# main_v2.net
KiCad netlist of a schematic drawn in EAGLE
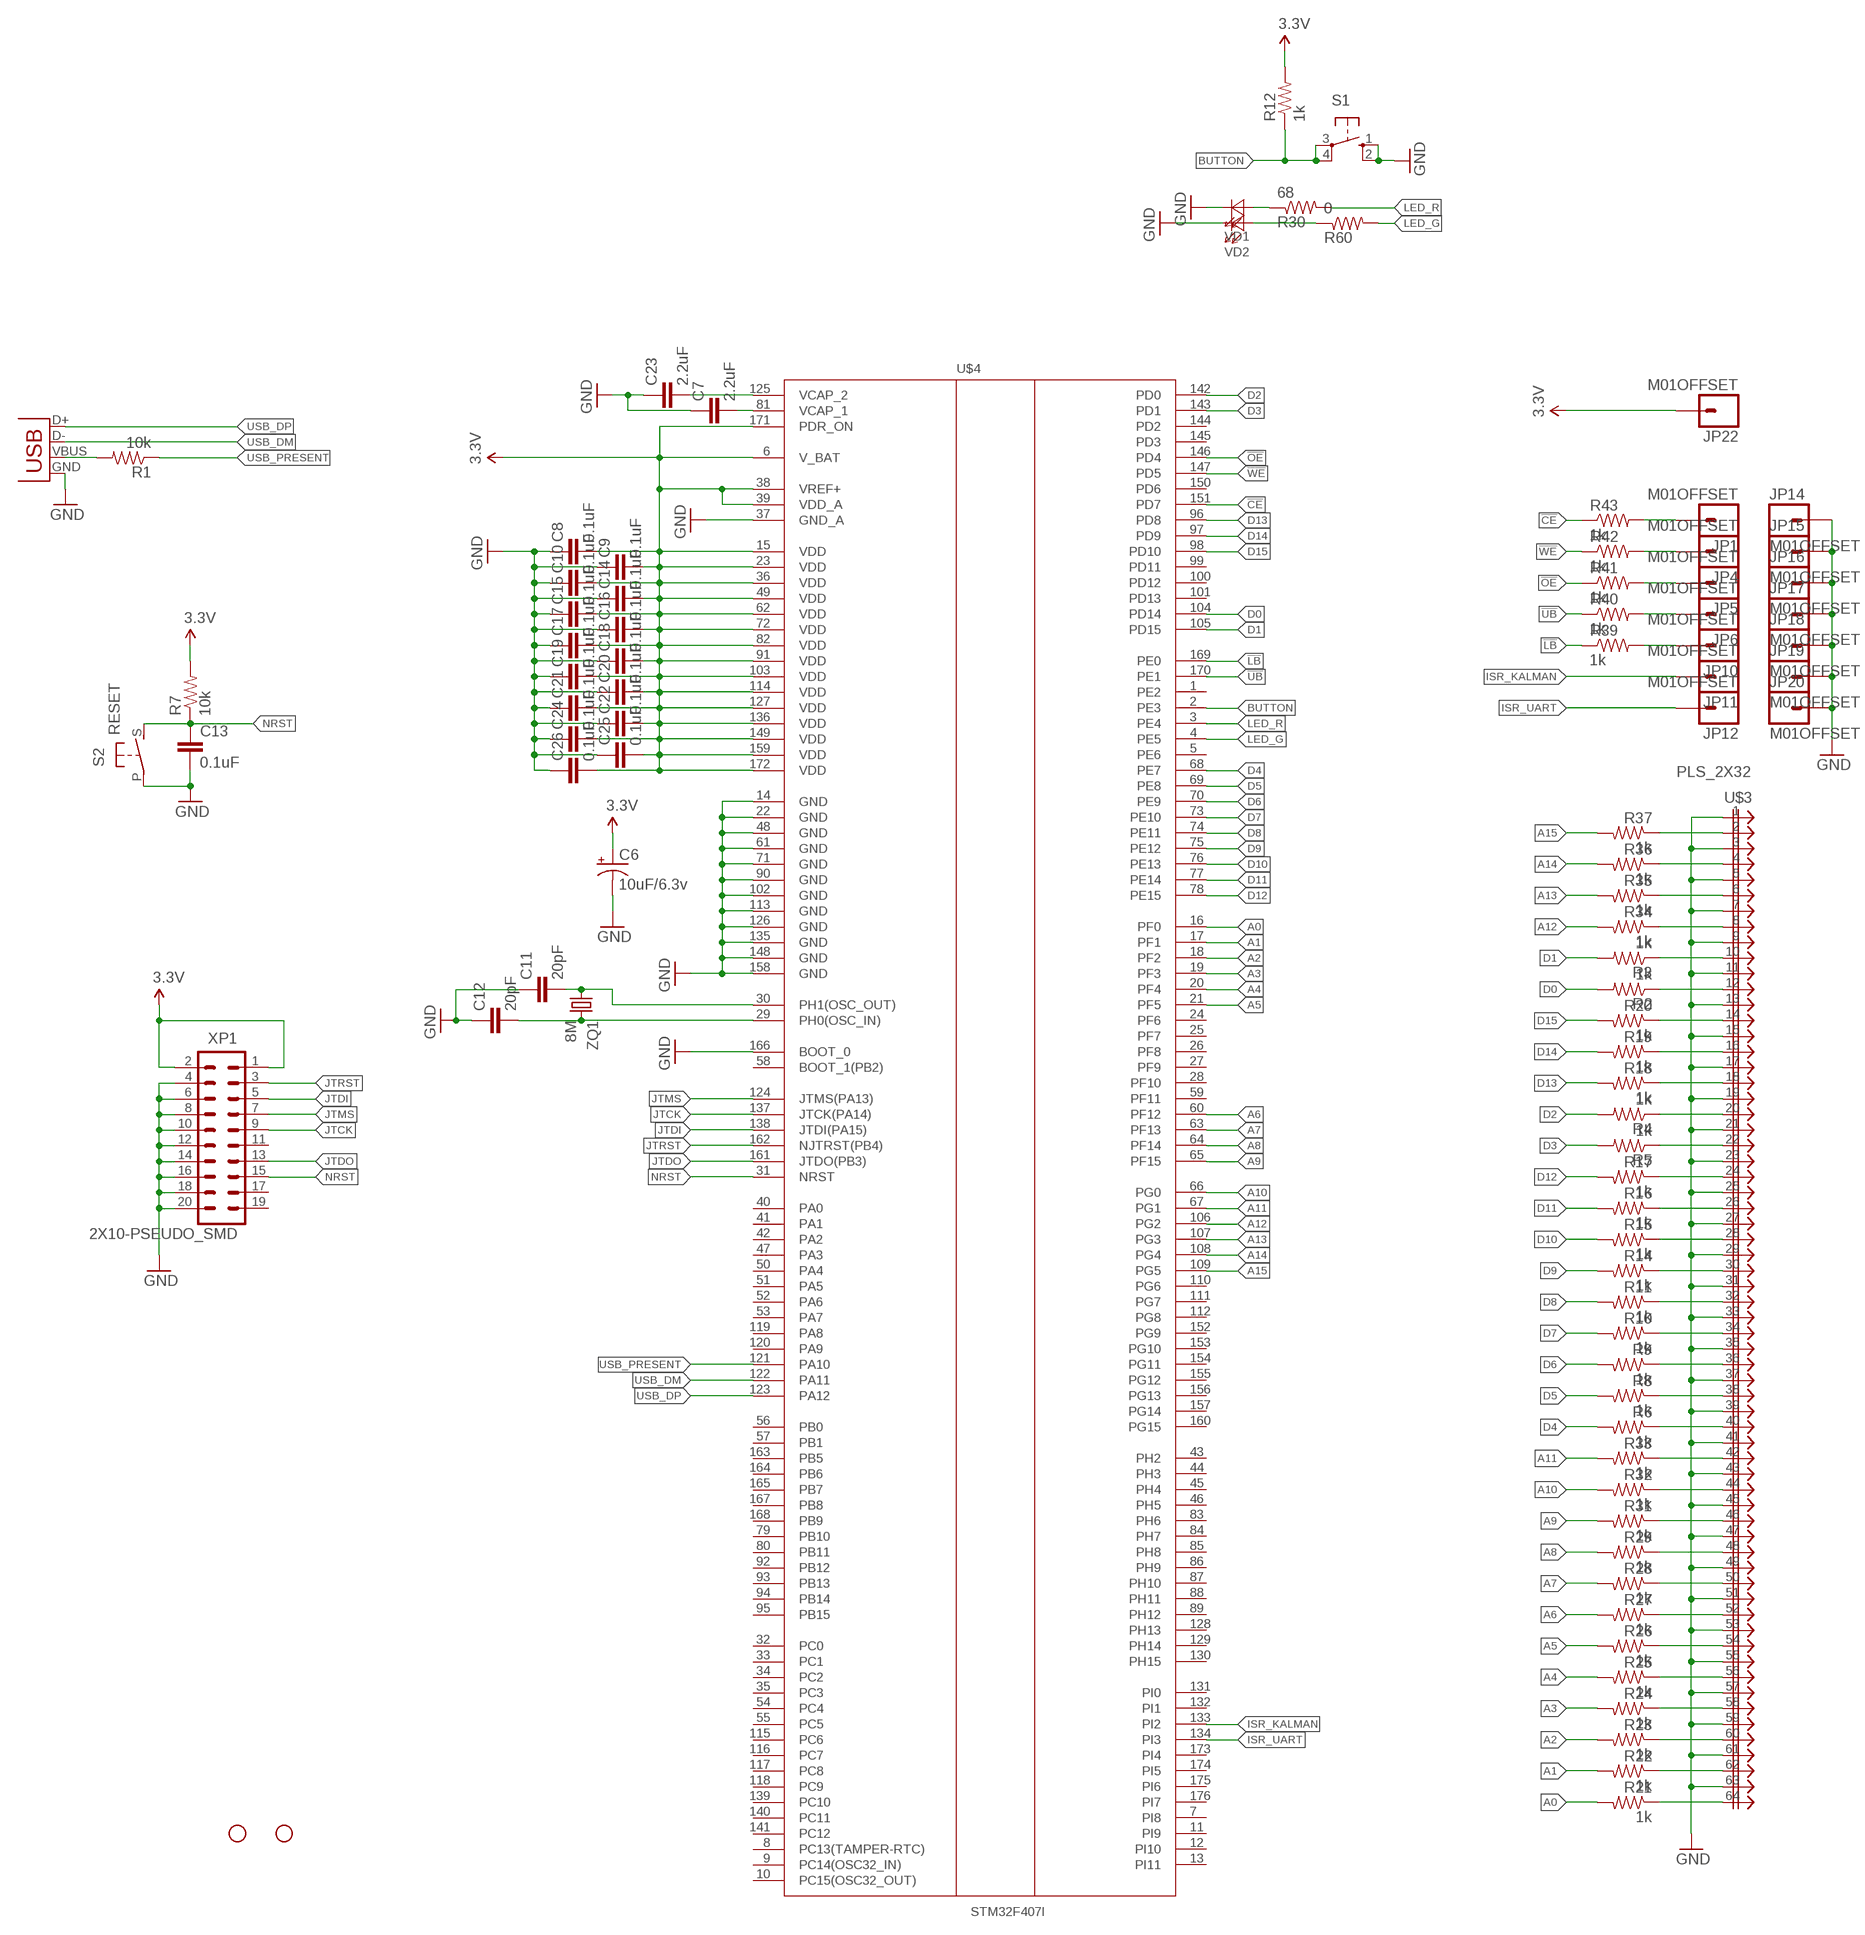
[diagram p0: schematic, sheet 1]

(export (version "E")
  (design (tool "Eeschema 10.0.6"))
  (components
    (comp (ref "C6")
      (value "10uF/6.3v")
      (footprint "eagle-import:EIA3216-KIT")
      (libsource (lib "eagle-import") (part "CAP_POL1206-KIT"))
    )
    (comp (ref "C7")
      (value "2.2uF")
      (footprint "eagle-import:0805")
      (libsource (lib "eagle-import") (part "CAP0805"))
    )
    (comp (ref "C8")
      (value "0.1uF")
      (footprint "eagle-import:0805")
      (libsource (lib "eagle-import") (part "CAP0805"))
    )
    (comp (ref "C9")
      (value "0.1uF")
      (footprint "eagle-import:0805")
      (libsource (lib "eagle-import") (part "CAP0805"))
    )
    (comp (ref "C10")
      (value "0.1uF")
      (footprint "eagle-import:0805")
      (libsource (lib "eagle-import") (part "CAP0805"))
    )
    (comp (ref "C11")
      (value "20pF")
      (footprint "eagle-import:0805")
      (libsource (lib "eagle-import") (part "CAP0805"))
    )
    (comp (ref "C12")
      (value "20pF")
      (footprint "eagle-import:0805")
      (libsource (lib "eagle-import") (part "CAP0805"))
    )
    (comp (ref "C13")
      (value "0.1uF")
      (footprint "eagle-import:0805")
      (libsource (lib "eagle-import") (part "CAP0805"))
    )
    (comp (ref "C14")
      (value "0.1uF")
      (footprint "eagle-import:0805")
      (libsource (lib "eagle-import") (part "CAP0805"))
    )
    (comp (ref "C15")
      (value "0.1uF")
      (footprint "eagle-import:0805")
      (libsource (lib "eagle-import") (part "CAP0805"))
    )
    (comp (ref "C16")
      (value "0.1uF")
      (footprint "eagle-import:0805")
      (libsource (lib "eagle-import") (part "CAP0805"))
    )
    (comp (ref "C17")
      (value "0.1uF")
      (footprint "eagle-import:0805")
      (libsource (lib "eagle-import") (part "CAP0805"))
    )
    (comp (ref "C18")
      (value "0.1uF")
      (footprint "eagle-import:0805")
      (libsource (lib "eagle-import") (part "CAP0805"))
    )
    (comp (ref "C19")
      (value "0.1uF")
      (footprint "eagle-import:0805")
      (libsource (lib "eagle-import") (part "CAP0805"))
    )
    (comp (ref "C20")
      (value "0.1uF")
      (footprint "eagle-import:0805")
      (libsource (lib "eagle-import") (part "CAP0805"))
    )
    (comp (ref "C21")
      (value "0.1uF")
      (footprint "eagle-import:0805")
      (libsource (lib "eagle-import") (part "CAP0805"))
    )
    (comp (ref "C22")
      (value "0.1uF")
      (footprint "eagle-import:0805")
      (libsource (lib "eagle-import") (part "CAP0805"))
    )
    (comp (ref "C23")
      (value "2.2uF")
      (footprint "eagle-import:0805")
      (libsource (lib "eagle-import") (part "CAP0805"))
    )
    (comp (ref "C24")
      (value "0.1uF")
      (footprint "eagle-import:0805")
      (libsource (lib "eagle-import") (part "CAP0805"))
    )
    (comp (ref "C25")
      (value "0.1uF")
      (footprint "eagle-import:0805")
      (libsource (lib "eagle-import") (part "CAP0805"))
    )
    (comp (ref "C26")
      (value "0.1uF")
      (footprint "eagle-import:0805")
      (libsource (lib "eagle-import") (part "CAP0805"))
    )
    (comp (ref "JP1")
      (value "M01OFFSET")
      (footprint "eagle-import:1X01_OFFSET")
      (libsource (lib "eagle-import") (part "M01OFFSET"))
    )
    (comp (ref "JP4")
      (value "M01OFFSET")
      (footprint "eagle-import:1X01_OFFSET")
      (libsource (lib "eagle-import") (part "M01OFFSET"))
    )
    (comp (ref "JP5")
      (value "M01OFFSET")
      (footprint "eagle-import:1X01_OFFSET")
      (libsource (lib "eagle-import") (part "M01OFFSET"))
    )
    (comp (ref "JP6")
      (value "M01OFFSET")
      (footprint "eagle-import:1X01_OFFSET")
      (libsource (lib "eagle-import") (part "M01OFFSET"))
    )
    (comp (ref "JP7")
      (value "STAND-OFF")
      (footprint "eagle-import:STAND-OFF")
      (libsource (lib "eagle-import") (part "STAND-OFF"))
    )
    (comp (ref "JP8")
      (value "STAND-OFF")
      (footprint "eagle-import:STAND-OFF")
      (libsource (lib "eagle-import") (part "STAND-OFF"))
    )
    (comp (ref "JP10")
      (value "M01OFFSET")
      (footprint "eagle-import:1X01_OFFSET")
      (libsource (lib "eagle-import") (part "M01OFFSET"))
    )
    (comp (ref "JP11")
      (value "M01OFFSET")
      (footprint "eagle-import:1X01_OFFSET")
      (libsource (lib "eagle-import") (part "M01OFFSET"))
    )
    (comp (ref "JP12")
      (value "M01OFFSET")
      (footprint "eagle-import:1X01_OFFSET")
      (libsource (lib "eagle-import") (part "M01OFFSET"))
    )
    (comp (ref "JP14")
      (value "M01OFFSET")
      (footprint "eagle-import:1X01_OFFSET")
      (libsource (lib "eagle-import") (part "M01OFFSET"))
    )
    (comp (ref "JP15")
      (value "M01OFFSET")
      (footprint "eagle-import:1X01_OFFSET")
      (libsource (lib "eagle-import") (part "M01OFFSET"))
    )
    (comp (ref "JP16")
      (value "M01OFFSET")
      (footprint "eagle-import:1X01_OFFSET")
      (libsource (lib "eagle-import") (part "M01OFFSET"))
    )
    (comp (ref "JP17")
      (value "M01OFFSET")
      (footprint "eagle-import:1X01_OFFSET")
      (libsource (lib "eagle-import") (part "M01OFFSET"))
    )
    (comp (ref "JP18")
      (value "M01OFFSET")
      (footprint "eagle-import:1X01_OFFSET")
      (libsource (lib "eagle-import") (part "M01OFFSET"))
    )
    (comp (ref "JP19")
      (value "M01OFFSET")
      (footprint "eagle-import:1X01_OFFSET")
      (libsource (lib "eagle-import") (part "M01OFFSET"))
    )
    (comp (ref "JP20")
      (value "M01OFFSET")
      (footprint "eagle-import:1X01_OFFSET")
      (libsource (lib "eagle-import") (part "M01OFFSET"))
    )
    (comp (ref "JP22")
      (value "M01OFFSET")
      (footprint "eagle-import:1X01_OFFSET")
      (libsource (lib "eagle-import") (part "M01OFFSET"))
    )
    (comp (ref "R1")
      (value "10k")
      (footprint "eagle-import:0805")
      (libsource (lib "eagle-import") (part "RESISTOR0805-RES"))
    )
    (comp (ref "R2")
      (value "1k")
      (footprint "eagle-import:0805")
      (libsource (lib "eagle-import") (part "RESISTOR0805-RES"))
    )
    (comp (ref "R3")
      (value "1k")
      (footprint "eagle-import:0805")
      (libsource (lib "eagle-import") (part "RESISTOR0805-RES"))
    )
    (comp (ref "R4")
      (value "1k")
      (footprint "eagle-import:0805")
      (libsource (lib "eagle-import") (part "RESISTOR0805-RES"))
    )
    (comp (ref "R5")
      (value "1k")
      (footprint "eagle-import:0805")
      (libsource (lib "eagle-import") (part "RESISTOR0805-RES"))
    )
    (comp (ref "R6")
      (value "1k")
      (footprint "eagle-import:0805")
      (libsource (lib "eagle-import") (part "RESISTOR0805-RES"))
    )
    (comp (ref "R7")
      (value "10k")
      (footprint "eagle-import:0805")
      (libsource (lib "eagle-import") (part "RESISTOR0805-RES"))
    )
    (comp (ref "R8")
      (value "1k")
      (footprint "eagle-import:0805")
      (libsource (lib "eagle-import") (part "RESISTOR0805-RES"))
    )
    (comp (ref "R9")
      (value "1k")
      (footprint "eagle-import:0805")
      (libsource (lib "eagle-import") (part "RESISTOR0805-RES"))
    )
    (comp (ref "R10")
      (value "1k")
      (footprint "eagle-import:0805")
      (libsource (lib "eagle-import") (part "RESISTOR0805-RES"))
    )
    (comp (ref "R11")
      (value "1k")
      (footprint "eagle-import:0805")
      (libsource (lib "eagle-import") (part "RESISTOR0805-RES"))
    )
    (comp (ref "R12")
      (value "1k")
      (footprint "eagle-import:0805")
      (libsource (lib "eagle-import") (part "RESISTOR0805-RES"))
    )
    (comp (ref "R14")
      (value "1k")
      (footprint "eagle-import:0805")
      (libsource (lib "eagle-import") (part "RESISTOR0805-RES"))
    )
    (comp (ref "R15")
      (value "1k")
      (footprint "eagle-import:0805")
      (libsource (lib "eagle-import") (part "RESISTOR0805-RES"))
    )
    (comp (ref "R16")
      (value "1k")
      (footprint "eagle-import:0805")
      (libsource (lib "eagle-import") (part "RESISTOR0805-RES"))
    )
    (comp (ref "R17")
      (value "1k")
      (footprint "eagle-import:0805")
      (libsource (lib "eagle-import") (part "RESISTOR0805-RES"))
    )
    (comp (ref "R18")
      (value "1k")
      (footprint "eagle-import:0805")
      (libsource (lib "eagle-import") (part "RESISTOR0805-RES"))
    )
    (comp (ref "R19")
      (value "1k")
      (footprint "eagle-import:0805")
      (libsource (lib "eagle-import") (part "RESISTOR0805-RES"))
    )
    (comp (ref "R20")
      (value "1k")
      (footprint "eagle-import:0805")
      (libsource (lib "eagle-import") (part "RESISTOR0805-RES"))
    )
    (comp (ref "R21")
      (value "1k")
      (footprint "eagle-import:0805")
      (libsource (lib "eagle-import") (part "RESISTOR0805-RES"))
    )
    (comp (ref "R22")
      (value "1k")
      (footprint "eagle-import:0805")
      (libsource (lib "eagle-import") (part "RESISTOR0805-RES"))
    )
    (comp (ref "R23")
      (value "1k")
      (footprint "eagle-import:0805")
      (libsource (lib "eagle-import") (part "RESISTOR0805-RES"))
    )
    (comp (ref "R24")
      (value "1k")
      (footprint "eagle-import:0805")
      (libsource (lib "eagle-import") (part "RESISTOR0805-RES"))
    )
    (comp (ref "R25")
      (value "1k")
      (footprint "eagle-import:0805")
      (libsource (lib "eagle-import") (part "RESISTOR0805-RES"))
    )
    (comp (ref "R26")
      (value "1k")
      (footprint "eagle-import:0805")
      (libsource (lib "eagle-import") (part "RESISTOR0805-RES"))
    )
    (comp (ref "R27")
      (value "1k")
      (footprint "eagle-import:0805")
      (libsource (lib "eagle-import") (part "RESISTOR0805-RES"))
    )
    (comp (ref "R28")
      (value "1k")
      (footprint "eagle-import:0805")
      (libsource (lib "eagle-import") (part "RESISTOR0805-RES"))
    )
    (comp (ref "R29")
      (value "1k")
      (footprint "eagle-import:0805")
      (libsource (lib "eagle-import") (part "RESISTOR0805-RES"))
    )
    (comp (ref "R30")
      (value "68")
      (footprint "eagle-import:0805")
      (libsource (lib "eagle-import") (part "RESISTOR0805-RES"))
    )
    (comp (ref "R31")
      (value "1k")
      (footprint "eagle-import:0805")
      (libsource (lib "eagle-import") (part "RESISTOR0805-RES"))
    )
    (comp (ref "R32")
      (value "1k")
      (footprint "eagle-import:0805")
      (libsource (lib "eagle-import") (part "RESISTOR0805-RES"))
    )
    (comp (ref "R33")
      (value "1k")
      (footprint "eagle-import:0805")
      (libsource (lib "eagle-import") (part "RESISTOR0805-RES"))
    )
    (comp (ref "R34")
      (value "1k")
      (footprint "eagle-import:0805")
      (libsource (lib "eagle-import") (part "RESISTOR0805-RES"))
    )
    (comp (ref "R35")
      (value "1k")
      (footprint "eagle-import:0805")
      (libsource (lib "eagle-import") (part "RESISTOR0805-RES"))
    )
    (comp (ref "R36")
      (value "1k")
      (footprint "eagle-import:0805")
      (libsource (lib "eagle-import") (part "RESISTOR0805-RES"))
    )
    (comp (ref "R37")
      (value "1k")
      (footprint "eagle-import:0805")
      (libsource (lib "eagle-import") (part "RESISTOR0805-RES"))
    )
    (comp (ref "R39")
      (value "1k")
      (footprint "eagle-import:0805")
      (libsource (lib "eagle-import") (part "RESISTOR0805-RES"))
    )
    (comp (ref "R40")
      (value "1k")
      (footprint "eagle-import:0805")
      (libsource (lib "eagle-import") (part "RESISTOR0805-RES"))
    )
    (comp (ref "R41")
      (value "1k")
      (footprint "eagle-import:0805")
      (libsource (lib "eagle-import") (part "RESISTOR0805-RES"))
    )
    (comp (ref "R42")
      (value "1k")
      (footprint "eagle-import:0805")
      (libsource (lib "eagle-import") (part "RESISTOR0805-RES"))
    )
    (comp (ref "R43")
      (value "1k")
      (footprint "eagle-import:0805")
      (libsource (lib "eagle-import") (part "RESISTOR0805-RES"))
    )
    (comp (ref "R60")
      (value "0")
      (footprint "eagle-import:0805")
      (libsource (lib "eagle-import") (part "RESISTOR0805-RES"))
    )
    (comp (ref "S1")
      (value "10-XX")
      (footprint "eagle-import:B3F-10XX")
      (fields (field (name "MPN") "B3F-1000"))
      (libsource (lib "eagle-import") (part "10-XX"))
    )
    (comp (ref "S2")
      (value "RESET")
      (footprint "eagle-import:BUTTON_6X3.5")
      (libsource (lib "eagle-import") (part "BUTTON_6X3.5"))
    )
    (comp (ref "U$3")
      (value "PLS_2X32")
      (footprint "eagle-import:PLS_2X32_PSEUDOSMD")
      (libsource (lib "eagle-import") (part "PLS_2X32"))
    )
    (comp (ref "U$4")
      (value "STM32F407I")
      (footprint "eagle-import:TQFP176(1.5X0.25)")
      (libsource (lib "eagle-import") (part "STM32F407I"))
    )
    (comp (ref "VD1")
      (value "LED1206")
      (footprint "eagle-import:LED-1206")
      (libsource (lib "eagle-import") (part "LED1206"))
    )
    (comp (ref "VD2")
      (value "LED1206")
      (footprint "eagle-import:LED-1206")
      (libsource (lib "eagle-import") (part "LED1206"))
    )
    (comp (ref "X1")
      (value "USB-SMD-NS")
      (footprint "eagle-import:USB-MINIB-NOSTOP")
      (libsource (lib "eagle-import") (part "USB-SMD-NS"))
    )
    (comp (ref "XP1")
      (value "2X10-PSEUDO_SMD")
      (footprint "eagle-import:PLD_2X10_PSEUDOSMD")
      (libsource (lib "eagle-import") (part "2X10-PSEUDO_SMD"))
    )
    (comp (ref "ZQ1")
      (value "8M")
      (footprint "eagle-import:CTS406")
      (libsource (lib "eagle-import") (part "CRYSTALCTS406"))
    )
  )
  (nets
    (net (code "1") (name "/~{CE}") (class "Default")
      (node (ref "R43") (pin "1") (pinfunction "1_1") (pintype "passive"))
      (node (ref "U$4") (pin "151") (pinfunction "PD7_151") (pintype "bidirectional"))
    )
    (net (code "2") (name "/~{LB}") (class "Default")
      (node (ref "R39") (pin "1") (pinfunction "1_1") (pintype "passive"))
      (node (ref "U$4") (pin "169") (pinfunction "PE0_169") (pintype "bidirectional"))
    )
    (net (code "3") (name "/~{OE}") (class "Default")
      (node (ref "R41") (pin "1") (pinfunction "1_1") (pintype "passive"))
      (node (ref "U$4") (pin "146") (pinfunction "PD4_146") (pintype "bidirectional"))
    )
    (net (code "4") (name "/~{UB}") (class "Default")
      (node (ref "R40") (pin "1") (pinfunction "1_1") (pintype "passive"))
      (node (ref "U$4") (pin "170") (pinfunction "PE1_170") (pintype "bidirectional"))
    )
    (net (code "5") (name "/~{WE}") (class "Default")
      (node (ref "R42") (pin "1") (pinfunction "1_1") (pintype "passive"))
      (node (ref "U$4") (pin "147") (pinfunction "PD5_147") (pintype "bidirectional"))
    )
    (net (code "6") (name "3.3V") (class "Default")
      (node (ref "C10") (pin "2") (pinfunction "2_2") (pintype "passive"))
      (node (ref "C14") (pin "2") (pinfunction "2_2") (pintype "passive"))
      (node (ref "C15") (pin "2") (pinfunction "2_2") (pintype "passive"))
      (node (ref "C16") (pin "2") (pinfunction "2_2") (pintype "passive"))
      (node (ref "C17") (pin "2") (pinfunction "2_2") (pintype "passive"))
      (node (ref "C18") (pin "2") (pinfunction "2_2") (pintype "passive"))
      (node (ref "C19") (pin "2") (pinfunction "2_2") (pintype "passive"))
      (node (ref "C20") (pin "2") (pinfunction "2_2") (pintype "passive"))
      (node (ref "C21") (pin "2") (pinfunction "2_2") (pintype "passive"))
      (node (ref "C22") (pin "2") (pinfunction "2_2") (pintype "passive"))
      (node (ref "C24") (pin "2") (pinfunction "2_2") (pintype "passive"))
      (node (ref "C25") (pin "2") (pinfunction "2_2") (pintype "passive"))
      (node (ref "C26") (pin "2") (pinfunction "2_2") (pintype "passive"))
      (node (ref "C6") (pin "A") (pinfunction "+_A") (pintype "passive"))
      (node (ref "C8") (pin "2") (pinfunction "2_2") (pintype "passive"))
      (node (ref "C9") (pin "2") (pinfunction "2_2") (pintype "passive"))
      (node (ref "JP22") (pin "1") (pinfunction "1_1") (pintype "passive"))
      (node (ref "R12") (pin "2") (pinfunction "2_2") (pintype "passive"))
      (node (ref "R7") (pin "2") (pinfunction "2_2") (pintype "passive"))
      (node (ref "U$4") (pin "103") (pinfunction "VDD_103") (pintype "power_in"))
      (node (ref "U$4") (pin "114") (pinfunction "VDD_114") (pintype "power_in"))
      (node (ref "U$4") (pin "127") (pinfunction "VDD_127") (pintype "power_in"))
      (node (ref "U$4") (pin "136") (pinfunction "VDD_136") (pintype "power_in"))
      (node (ref "U$4") (pin "149") (pinfunction "VDD_149") (pintype "power_in"))
      (node (ref "U$4") (pin "15") (pinfunction "VDD_15") (pintype "power_in"))
      (node (ref "U$4") (pin "159") (pinfunction "VDD_159") (pintype "power_in"))
      (node (ref "U$4") (pin "171") (pinfunction "PDR_ON_171") (pintype "power_in"))
      (node (ref "U$4") (pin "172") (pinfunction "VDD_172") (pintype "power_in"))
      (node (ref "U$4") (pin "23") (pinfunction "VDD_23") (pintype "power_in"))
      (node (ref "U$4") (pin "36") (pinfunction "VDD_36") (pintype "power_in"))
      (node (ref "U$4") (pin "38") (pinfunction "VREF+_38") (pintype "power_in"))
      (node (ref "U$4") (pin "39") (pinfunction "VDD_A_39") (pintype "power_in"))
      (node (ref "U$4") (pin "49") (pinfunction "VDD_49") (pintype "power_in"))
      (node (ref "U$4") (pin "6") (pinfunction "V_BAT_6") (pintype "power_in"))
      (node (ref "U$4") (pin "62") (pinfunction "VDD_62") (pintype "power_in"))
      (node (ref "U$4") (pin "72") (pinfunction "VDD_72") (pintype "power_in"))
      (node (ref "U$4") (pin "82") (pinfunction "VDD_82") (pintype "power_in"))
      (node (ref "U$4") (pin "91") (pinfunction "VDD_91") (pintype "power_in"))
      (node (ref "XP1") (pin "1") (pinfunction "1_1") (pintype "passive"))
      (node (ref "XP1") (pin "2") (pinfunction "2_2") (pintype "passive"))
    )
    (net (code "7") (name "A0") (class "Default")
      (node (ref "R21") (pin "2") (pinfunction "2_2") (pintype "passive"))
      (node (ref "U$4") (pin "16") (pinfunction "PF0_16") (pintype "bidirectional"))
    )
    (net (code "8") (name "A1") (class "Default")
      (node (ref "R22") (pin "2") (pinfunction "2_2") (pintype "passive"))
      (node (ref "U$4") (pin "17") (pinfunction "PF1_17") (pintype "bidirectional"))
    )
    (net (code "9") (name "A2") (class "Default")
      (node (ref "R23") (pin "2") (pinfunction "2_2") (pintype "passive"))
      (node (ref "U$4") (pin "18") (pinfunction "PF2_18") (pintype "bidirectional"))
    )
    (net (code "10") (name "A3") (class "Default")
      (node (ref "R24") (pin "2") (pinfunction "2_2") (pintype "passive"))
      (node (ref "U$4") (pin "19") (pinfunction "PF3_19") (pintype "bidirectional"))
    )
    (net (code "11") (name "A4") (class "Default")
      (node (ref "R25") (pin "2") (pinfunction "2_2") (pintype "passive"))
      (node (ref "U$4") (pin "20") (pinfunction "PF4_20") (pintype "bidirectional"))
    )
    (net (code "12") (name "A5") (class "Default")
      (node (ref "R26") (pin "2") (pinfunction "2_2") (pintype "passive"))
      (node (ref "U$4") (pin "21") (pinfunction "PF5_21") (pintype "bidirectional"))
    )
    (net (code "13") (name "A6") (class "Default")
      (node (ref "R27") (pin "2") (pinfunction "2_2") (pintype "passive"))
      (node (ref "U$4") (pin "60") (pinfunction "PF12_60") (pintype "bidirectional"))
    )
    (net (code "14") (name "A7") (class "Default")
      (node (ref "R28") (pin "2") (pinfunction "2_2") (pintype "passive"))
      (node (ref "U$4") (pin "63") (pinfunction "PF13_63") (pintype "bidirectional"))
    )
    (net (code "15") (name "A8") (class "Default")
      (node (ref "R29") (pin "2") (pinfunction "2_2") (pintype "passive"))
      (node (ref "U$4") (pin "64") (pinfunction "PF14_64") (pintype "bidirectional"))
    )
    (net (code "16") (name "A9") (class "Default")
      (node (ref "R31") (pin "2") (pinfunction "2_2") (pintype "passive"))
      (node (ref "U$4") (pin "65") (pinfunction "PF15_65") (pintype "bidirectional"))
    )
    (net (code "17") (name "A10") (class "Default")
      (node (ref "R32") (pin "2") (pinfunction "2_2") (pintype "passive"))
      (node (ref "U$4") (pin "66") (pinfunction "PG0_66") (pintype "bidirectional"))
    )
    (net (code "18") (name "A11") (class "Default")
      (node (ref "R33") (pin "2") (pinfunction "2_2") (pintype "passive"))
      (node (ref "U$4") (pin "67") (pinfunction "PG1_67") (pintype "bidirectional"))
    )
    (net (code "19") (name "A12") (class "Default")
      (node (ref "R34") (pin "2") (pinfunction "2_2") (pintype "passive"))
      (node (ref "U$4") (pin "106") (pinfunction "PG2_106") (pintype "bidirectional"))
    )
    (net (code "20") (name "A13") (class "Default")
      (node (ref "R35") (pin "2") (pinfunction "2_2") (pintype "passive"))
      (node (ref "U$4") (pin "107") (pinfunction "PG3_107") (pintype "bidirectional"))
    )
    (net (code "21") (name "A14") (class "Default")
      (node (ref "R36") (pin "2") (pinfunction "2_2") (pintype "passive"))
      (node (ref "U$4") (pin "108") (pinfunction "PG4_108") (pintype "bidirectional"))
    )
    (net (code "22") (name "A15") (class "Default")
      (node (ref "R37") (pin "2") (pinfunction "2_2") (pintype "passive"))
      (node (ref "U$4") (pin "109") (pinfunction "PG5_109") (pintype "bidirectional"))
    )
    (net (code "23") (name "BUTTON") (class "Default")
      (node (ref "R12") (pin "1") (pinfunction "1_1") (pintype "passive"))
      (node (ref "S1") (pin "3") (pinfunction "P_3") (pintype "passive"))
      (node (ref "S1") (pin "4") (pinfunction "P1_4") (pintype "passive"))
      (node (ref "U$4") (pin "2") (pinfunction "PE3_2") (pintype "bidirectional"))
    )
    (net (code "24") (name "D0") (class "Default")
      (node (ref "R2") (pin "2") (pinfunction "2_2") (pintype "passive"))
      (node (ref "U$4") (pin "104") (pinfunction "PD14_104") (pintype "bidirectional"))
    )
    (net (code "25") (name "D1") (class "Default")
      (node (ref "R3") (pin "2") (pinfunction "2_2") (pintype "passive"))
      (node (ref "U$4") (pin "105") (pinfunction "PD15_105") (pintype "bidirectional"))
    )
    (net (code "26") (name "D2") (class "Default")
      (node (ref "R4") (pin "2") (pinfunction "2_2") (pintype "passive"))
      (node (ref "U$4") (pin "142") (pinfunction "PD0_142") (pintype "bidirectional"))
    )
    (net (code "27") (name "D3") (class "Default")
      (node (ref "R5") (pin "2") (pinfunction "2_2") (pintype "passive"))
      (node (ref "U$4") (pin "143") (pinfunction "PD1_143") (pintype "bidirectional"))
    )
    (net (code "28") (name "D4") (class "Default")
      (node (ref "R6") (pin "2") (pinfunction "2_2") (pintype "passive"))
      (node (ref "U$4") (pin "68") (pinfunction "PE7_68") (pintype "bidirectional"))
    )
    (net (code "29") (name "D5") (class "Default")
      (node (ref "R8") (pin "2") (pinfunction "2_2") (pintype "passive"))
      (node (ref "U$4") (pin "69") (pinfunction "PE8_69") (pintype "bidirectional"))
    )
    (net (code "30") (name "D6") (class "Default")
      (node (ref "R9") (pin "2") (pinfunction "2_2") (pintype "passive"))
      (node (ref "U$4") (pin "70") (pinfunction "PE9_70") (pintype "bidirectional"))
    )
    (net (code "31") (name "D7") (class "Default")
      (node (ref "R10") (pin "2") (pinfunction "2_2") (pintype "passive"))
      (node (ref "U$4") (pin "73") (pinfunction "PE10_73") (pintype "bidirectional"))
    )
    (net (code "32") (name "D8") (class "Default")
      (node (ref "R11") (pin "2") (pinfunction "2_2") (pintype "passive"))
      (node (ref "U$4") (pin "74") (pinfunction "PE11_74") (pintype "bidirectional"))
    )
    (net (code "33") (name "D9") (class "Default")
      (node (ref "R14") (pin "2") (pinfunction "2_2") (pintype "passive"))
      (node (ref "U$4") (pin "75") (pinfunction "PE12_75") (pintype "bidirectional"))
    )
    (net (code "34") (name "D10") (class "Default")
      (node (ref "R15") (pin "2") (pinfunction "2_2") (pintype "passive"))
      (node (ref "U$4") (pin "76") (pinfunction "PE13_76") (pintype "bidirectional"))
    )
    (net (code "35") (name "D11") (class "Default")
      (node (ref "R16") (pin "2") (pinfunction "2_2") (pintype "passive"))
      (node (ref "U$4") (pin "77") (pinfunction "PE14_77") (pintype "bidirectional"))
    )
    (net (code "36") (name "D12") (class "Default")
      (node (ref "R17") (pin "2") (pinfunction "2_2") (pintype "passive"))
      (node (ref "U$4") (pin "78") (pinfunction "PE15_78") (pintype "bidirectional"))
    )
    (net (code "37") (name "D13") (class "Default")
      (node (ref "R18") (pin "2") (pinfunction "2_2") (pintype "passive"))
      (node (ref "U$4") (pin "96") (pinfunction "PD8_96") (pintype "bidirectional"))
    )
    (net (code "38") (name "D14") (class "Default")
      (node (ref "R19") (pin "2") (pinfunction "2_2") (pintype "passive"))
      (node (ref "U$4") (pin "97") (pinfunction "PD9_97") (pintype "bidirectional"))
    )
    (net (code "39") (name "D15") (class "Default")
      (node (ref "R20") (pin "2") (pinfunction "2_2") (pintype "passive"))
      (node (ref "U$4") (pin "98") (pinfunction "PD10_98") (pintype "bidirectional"))
    )
    (net (code "40") (name "GND") (class "Default")
      (node (ref "C10") (pin "1") (pinfunction "1_1") (pintype "passive"))
      (node (ref "C11") (pin "1") (pinfunction "1_1") (pintype "passive"))
      (node (ref "C12") (pin "1") (pinfunction "1_1") (pintype "passive"))
      (node (ref "C13") (pin "2") (pinfunction "2_2") (pintype "passive"))
      (node (ref "C14") (pin "1") (pinfunction "1_1") (pintype "passive"))
      (node (ref "C15") (pin "1") (pinfunction "1_1") (pintype "passive"))
      (node (ref "C16") (pin "1") (pinfunction "1_1") (pintype "passive"))
      (node (ref "C17") (pin "1") (pinfunction "1_1") (pintype "passive"))
      (node (ref "C18") (pin "1") (pinfunction "1_1") (pintype "passive"))
      (node (ref "C19") (pin "1") (pinfunction "1_1") (pintype "passive"))
      (node (ref "C20") (pin "1") (pinfunction "1_1") (pintype "passive"))
      (node (ref "C21") (pin "1") (pinfunction "1_1") (pintype "passive"))
      (node (ref "C22") (pin "1") (pinfunction "1_1") (pintype "passive"))
      (node (ref "C23") (pin "1") (pinfunction "1_1") (pintype "passive"))
      (node (ref "C24") (pin "1") (pinfunction "1_1") (pintype "passive"))
      (node (ref "C25") (pin "1") (pinfunction "1_1") (pintype "passive"))
      (node (ref "C26") (pin "1") (pinfunction "1_1") (pintype "passive"))
      (node (ref "C6") (pin "C") (pinfunction "-_C") (pintype "passive"))
      (node (ref "C7") (pin "1") (pinfunction "1_1") (pintype "passive"))
      (node (ref "C8") (pin "1") (pinfunction "1_1") (pintype "passive"))
      (node (ref "C9") (pin "1") (pinfunction "1_1") (pintype "passive"))
      (node (ref "JP14") (pin "1") (pinfunction "1_1") (pintype "passive"))
      (node (ref "JP15") (pin "1") (pinfunction "1_1") (pintype "passive"))
      (node (ref "JP16") (pin "1") (pinfunction "1_1") (pintype "passive"))
      (node (ref "JP17") (pin "1") (pinfunction "1_1") (pintype "passive"))
      (node (ref "JP18") (pin "1") (pinfunction "1_1") (pintype "passive"))
      (node (ref "JP19") (pin "1") (pinfunction "1_1") (pintype "passive"))
      (node (ref "JP20") (pin "1") (pinfunction "1_1") (pintype "passive"))
      (node (ref "S1") (pin "1") (pinfunction "S_1") (pintype "passive"))
      (node (ref "S1") (pin "2") (pinfunction "S1_2") (pintype "passive"))
      (node (ref "S2") (pin "P") (pinfunction "P_P") (pintype "passive"))
      (node (ref "U$3") (pin "1") (pinfunction "1_1") (pintype "passive"))
      (node (ref "U$3") (pin "11") (pinfunction "11_11") (pintype "passive"))
      (node (ref "U$3") (pin "13") (pinfunction "13_13") (pintype "passive"))
      (node (ref "U$3") (pin "15") (pinfunction "15_15") (pintype "passive"))
      (node (ref "U$3") (pin "17") (pinfunction "17_17") (pintype "passive"))
      (node (ref "U$3") (pin "19") (pinfunction "19_19") (pintype "passive"))
      (node (ref "U$3") (pin "21") (pinfunction "21_21") (pintype "passive"))
      (node (ref "U$3") (pin "23") (pinfunction "23_23") (pintype "passive"))
      (node (ref "U$3") (pin "25") (pinfunction "25_25") (pintype "passive"))
      (node (ref "U$3") (pin "27") (pinfunction "27_27") (pintype "passive"))
      (node (ref "U$3") (pin "29") (pinfunction "29_29") (pintype "passive"))
      (node (ref "U$3") (pin "3") (pinfunction "3_3") (pintype "passive"))
      (node (ref "U$3") (pin "31") (pinfunction "31_31") (pintype "passive"))
      (node (ref "U$3") (pin "33") (pinfunction "33_33") (pintype "passive"))
      (node (ref "U$3") (pin "35") (pinfunction "35_35") (pintype "passive"))
      (node (ref "U$3") (pin "37") (pinfunction "37_37") (pintype "passive"))
      (node (ref "U$3") (pin "39") (pinfunction "39_39") (pintype "passive"))
      (node (ref "U$3") (pin "41") (pinfunction "41_41") (pintype "passive"))
      (node (ref "U$3") (pin "43") (pinfunction "43_43") (pintype "passive"))
      (node (ref "U$3") (pin "45") (pinfunction "45_45") (pintype "passive"))
      (node (ref "U$3") (pin "47") (pinfunction "47_47") (pintype "passive"))
      (node (ref "U$3") (pin "49") (pinfunction "49_49") (pintype "passive"))
      (node (ref "U$3") (pin "5") (pinfunction "5_5") (pintype "passive"))
      (node (ref "U$3") (pin "51") (pinfunction "51_51") (pintype "passive"))
      (node (ref "U$3") (pin "53") (pinfunction "53_53") (pintype "passive"))
      (node (ref "U$3") (pin "55") (pinfunction "55_55") (pintype "passive"))
      (node (ref "U$3") (pin "57") (pinfunction "57_57") (pintype "passive"))
      (node (ref "U$3") (pin "59") (pinfunction "59_59") (pintype "passive"))
      (node (ref "U$3") (pin "61") (pinfunction "61_61") (pintype "passive"))
      (node (ref "U$3") (pin "63") (pinfunction "63_63") (pintype "passive"))
      (node (ref "U$3") (pin "7") (pinfunction "7_7") (pintype "passive"))
      (node (ref "U$3") (pin "9") (pinfunction "9_9") (pintype "passive"))
      (node (ref "U$4") (pin "102") (pinfunction "GND_102") (pintype "power_in"))
      (node (ref "U$4") (pin "113") (pinfunction "GND_113") (pintype "power_in"))
      (node (ref "U$4") (pin "126") (pinfunction "GND_126") (pintype "power_in"))
      (node (ref "U$4") (pin "135") (pinfunction "GND_135") (pintype "power_in"))
      (node (ref "U$4") (pin "14") (pinfunction "GND_14") (pintype "power_in"))
      (node (ref "U$4") (pin "148") (pinfunction "GND_148") (pintype "power_in"))
      (node (ref "U$4") (pin "158") (pinfunction "GND_158") (pintype "power_in"))
      (node (ref "U$4") (pin "166") (pinfunction "BOOT_0_166") (pintype "input"))
      (node (ref "U$4") (pin "22") (pinfunction "GND_22") (pintype "power_in"))
      (node (ref "U$4") (pin "37") (pinfunction "GND_A_37") (pintype "power_in"))
      (node (ref "U$4") (pin "48") (pinfunction "GND_48") (pintype "power_in"))
      (node (ref "U$4") (pin "61") (pinfunction "GND_61") (pintype "power_in"))
      (node (ref "U$4") (pin "71") (pinfunction "GND_71") (pintype "power_in"))
      (node (ref "U$4") (pin "90") (pinfunction "GND_90") (pintype "power_in"))
      (node (ref "VD1") (pin "C") (pinfunction "C_C") (pintype "passive"))
      (node (ref "VD2") (pin "C") (pinfunction "C_C") (pintype "passive"))
      (node (ref "X1") (pin "GND") (pinfunction "GND_GND") (pintype "bidirectional"))
      (node (ref "XP1") (pin "10") (pinfunction "10_10") (pintype "passive"))
      (node (ref "XP1") (pin "12") (pinfunction "12_12") (pintype "passive"))
      (node (ref "XP1") (pin "14") (pinfunction "14_14") (pintype "passive"))
      (node (ref "XP1") (pin "16") (pinfunction "16_16") (pintype "passive"))
      (node (ref "XP1") (pin "18") (pinfunction "18_18") (pintype "passive"))
      (node (ref "XP1") (pin "20") (pinfunction "20_20") (pintype "passive"))
      (node (ref "XP1") (pin "4") (pinfunction "4_4") (pintype "passive"))
      (node (ref "XP1") (pin "6") (pinfunction "6_6") (pintype "passive"))
      (node (ref "XP1") (pin "8") (pinfunction "8_8") (pintype "passive"))
    )
    (net (code "41") (name "ISR_KALMAN") (class "Default")
      (node (ref "JP11") (pin "1") (pinfunction "1_1") (pintype "passive"))
      (node (ref "U$4") (pin "133") (pinfunction "PI2_133") (pintype "bidirectional"))
    )
    (net (code "42") (name "ISR_UART") (class "Default")
      (node (ref "JP12") (pin "1") (pinfunction "1_1") (pintype "passive"))
      (node (ref "U$4") (pin "134") (pinfunction "PI3_134") (pintype "bidirectional"))
    )
    (net (code "43") (name "JTCK") (class "Default")
      (node (ref "U$4") (pin "137") (pinfunction "JTCK(PA14)_137") (pintype "bidirectional"))
      (node (ref "XP1") (pin "9") (pinfunction "9_9") (pintype "passive"))
    )
    (net (code "44") (name "JTDI") (class "Default")
      (node (ref "U$4") (pin "138") (pinfunction "JTDI(PA15)_138") (pintype "bidirectional"))
      (node (ref "XP1") (pin "5") (pinfunction "5_5") (pintype "passive"))
    )
    (net (code "45") (name "JTDO") (class "Default")
      (node (ref "U$4") (pin "161") (pinfunction "JTDO(PB3)_161") (pintype "bidirectional"))
      (node (ref "XP1") (pin "13") (pinfunction "13_13") (pintype "passive"))
    )
    (net (code "46") (name "JTMS") (class "Default")
      (node (ref "U$4") (pin "124") (pinfunction "JTMS(PA13)_124") (pintype "bidirectional"))
      (node (ref "XP1") (pin "7") (pinfunction "7_7") (pintype "passive"))
    )
    (net (code "47") (name "JTRST") (class "Default")
      (node (ref "U$4") (pin "162") (pinfunction "NJTRST(PB4)_162") (pintype "bidirectional"))
      (node (ref "XP1") (pin "3") (pinfunction "3_3") (pintype "passive"))
    )
    (net (code "48") (name "LED_G") (class "Default")
      (node (ref "R60") (pin "2") (pinfunction "2_2") (pintype "passive"))
      (node (ref "U$4") (pin "4") (pinfunction "PE5_4") (pintype "bidirectional"))
    )
    (net (code "49") (name "LED_R") (class "Default")
      (node (ref "R30") (pin "2") (pinfunction "2_2") (pintype "passive"))
      (node (ref "U$4") (pin "3") (pinfunction "PE4_3") (pintype "bidirectional"))
    )
    (net (code "50") (name "NRST") (class "Default")
      (node (ref "C13") (pin "1") (pinfunction "1_1") (pintype "passive"))
      (node (ref "R7") (pin "1") (pinfunction "1_1") (pintype "passive"))
      (node (ref "S2") (pin "S") (pinfunction "S_S") (pintype "passive"))
      (node (ref "U$4") (pin "31") (pinfunction "NRST_31") (pintype "bidirectional"))
      (node (ref "XP1") (pin "15") (pinfunction "15_15") (pintype "passive"))
    )
    (net (code "51") (name "Net-(JP1-Pad1)") (class "Default")
      (node (ref "JP1") (pin "1") (pinfunction "1_1") (pintype "passive"))
      (node (ref "R43") (pin "2") (pinfunction "2_2") (pintype "passive"))
    )
    (net (code "52") (name "Net-(JP4-Pad1)") (class "Default")
      (node (ref "JP4") (pin "1") (pinfunction "1_1") (pintype "passive"))
      (node (ref "R42") (pin "2") (pinfunction "2_2") (pintype "passive"))
    )
    (net (code "53") (name "Net-(JP5-Pad1)") (class "Default")
      (node (ref "JP5") (pin "1") (pinfunction "1_1") (pintype "passive"))
      (node (ref "R41") (pin "2") (pinfunction "2_2") (pintype "passive"))
    )
    (net (code "54") (name "Net-(JP6-Pad1)") (class "Default")
      (node (ref "JP6") (pin "1") (pinfunction "1_1") (pintype "passive"))
      (node (ref "R40") (pin "2") (pinfunction "2_2") (pintype "passive"))
    )
    (net (code "55") (name "Net-(JP10-Pad1)") (class "Default")
      (node (ref "JP10") (pin "1") (pinfunction "1_1") (pintype "passive"))
      (node (ref "R39") (pin "2") (pinfunction "2_2") (pintype "passive"))
    )
    (net (code "56") (name "Net-(R1-Pad2)") (class "Default")
      (node (ref "R1") (pin "2") (pinfunction "2_2") (pintype "passive"))
      (node (ref "X1") (pin "VBUS") (pinfunction "VBUS_VBUS") (pintype "bidirectional"))
    )
    (net (code "57") (name "Net-(R2-Pad1)") (class "Default")
      (node (ref "R2") (pin "1") (pinfunction "1_1") (pintype "passive"))
      (node (ref "U$3") (pin "12") (pinfunction "12_12") (pintype "passive"))
    )
    (net (code "58") (name "Net-(R3-Pad1)") (class "Default")
      (node (ref "R3") (pin "1") (pinfunction "1_1") (pintype "passive"))
      (node (ref "U$3") (pin "10") (pinfunction "10_10") (pintype "passive"))
    )
    (net (code "59") (name "Net-(R4-Pad1)") (class "Default")
      (node (ref "R4") (pin "1") (pinfunction "1_1") (pintype "passive"))
      (node (ref "U$3") (pin "20") (pinfunction "20_20") (pintype "passive"))
    )
    (net (code "60") (name "Net-(R5-Pad1)") (class "Default")
      (node (ref "R5") (pin "1") (pinfunction "1_1") (pintype "passive"))
      (node (ref "U$3") (pin "22") (pinfunction "22_22") (pintype "passive"))
    )
    (net (code "61") (name "Net-(R6-Pad1)") (class "Default")
      (node (ref "R6") (pin "1") (pinfunction "1_1") (pintype "passive"))
      (node (ref "U$3") (pin "40") (pinfunction "40_40") (pintype "passive"))
    )
    (net (code "62") (name "Net-(R8-Pad1)") (class "Default")
      (node (ref "R8") (pin "1") (pinfunction "1_1") (pintype "passive"))
      (node (ref "U$3") (pin "38") (pinfunction "38_38") (pintype "passive"))
    )
    (net (code "63") (name "Net-(R9-Pad1)") (class "Default")
      (node (ref "R9") (pin "1") (pinfunction "1_1") (pintype "passive"))
      (node (ref "U$3") (pin "36") (pinfunction "36_36") (pintype "passive"))
    )
    (net (code "64") (name "Net-(R10-Pad1)") (class "Default")
      (node (ref "R10") (pin "1") (pinfunction "1_1") (pintype "passive"))
      (node (ref "U$3") (pin "34") (pinfunction "34_34") (pintype "passive"))
    )
    (net (code "65") (name "Net-(R11-Pad1)") (class "Default")
      (node (ref "R11") (pin "1") (pinfunction "1_1") (pintype "passive"))
      (node (ref "U$3") (pin "32") (pinfunction "32_32") (pintype "passive"))
    )
    (net (code "66") (name "Net-(R14-Pad1)") (class "Default")
      (node (ref "R14") (pin "1") (pinfunction "1_1") (pintype "passive"))
      (node (ref "U$3") (pin "30") (pinfunction "30_30") (pintype "passive"))
    )
    (net (code "67") (name "Net-(R15-Pad1)") (class "Default")
      (node (ref "R15") (pin "1") (pinfunction "1_1") (pintype "passive"))
      (node (ref "U$3") (pin "28") (pinfunction "28_28") (pintype "passive"))
    )
    (net (code "68") (name "Net-(R16-Pad1)") (class "Default")
      (node (ref "R16") (pin "1") (pinfunction "1_1") (pintype "passive"))
      (node (ref "U$3") (pin "26") (pinfunction "26_26") (pintype "passive"))
    )
    (net (code "69") (name "Net-(R17-Pad1)") (class "Default")
      (node (ref "R17") (pin "1") (pinfunction "1_1") (pintype "passive"))
      (node (ref "U$3") (pin "24") (pinfunction "24_24") (pintype "passive"))
    )
    (net (code "70") (name "Net-(R18-Pad1)") (class "Default")
      (node (ref "R18") (pin "1") (pinfunction "1_1") (pintype "passive"))
      (node (ref "U$3") (pin "18") (pinfunction "18_18") (pintype "passive"))
    )
    (net (code "71") (name "Net-(R19-Pad1)") (class "Default")
      (node (ref "R19") (pin "1") (pinfunction "1_1") (pintype "passive"))
      (node (ref "U$3") (pin "16") (pinfunction "16_16") (pintype "passive"))
    )
    (net (code "72") (name "Net-(R20-Pad1)") (class "Default")
      (node (ref "R20") (pin "1") (pinfunction "1_1") (pintype "passive"))
      (node (ref "U$3") (pin "14") (pinfunction "14_14") (pintype "passive"))
    )
    (net (code "73") (name "Net-(R21-Pad1)") (class "Default")
      (node (ref "R21") (pin "1") (pinfunction "1_1") (pintype "passive"))
      (node (ref "U$3") (pin "64") (pinfunction "64_64") (pintype "passive"))
    )
    (net (code "74") (name "Net-(R22-Pad1)") (class "Default")
      (node (ref "R22") (pin "1") (pinfunction "1_1") (pintype "passive"))
      (node (ref "U$3") (pin "62") (pinfunction "62_62") (pintype "passive"))
    )
    (net (code "75") (name "Net-(R23-Pad1)") (class "Default")
      (node (ref "R23") (pin "1") (pinfunction "1_1") (pintype "passive"))
      (node (ref "U$3") (pin "60") (pinfunction "60_60") (pintype "passive"))
    )
    (net (code "76") (name "Net-(R24-Pad1)") (class "Default")
      (node (ref "R24") (pin "1") (pinfunction "1_1") (pintype "passive"))
      (node (ref "U$3") (pin "58") (pinfunction "58_58") (pintype "passive"))
    )
    (net (code "77") (name "Net-(R25-Pad1)") (class "Default")
      (node (ref "R25") (pin "1") (pinfunction "1_1") (pintype "passive"))
      (node (ref "U$3") (pin "56") (pinfunction "56_56") (pintype "passive"))
    )
    (net (code "78") (name "Net-(R26-Pad1)") (class "Default")
      (node (ref "R26") (pin "1") (pinfunction "1_1") (pintype "passive"))
      (node (ref "U$3") (pin "54") (pinfunction "54_54") (pintype "passive"))
    )
    (net (code "79") (name "Net-(R27-Pad1)") (class "Default")
      (node (ref "R27") (pin "1") (pinfunction "1_1") (pintype "passive"))
      (node (ref "U$3") (pin "52") (pinfunction "52_52") (pintype "passive"))
    )
    (net (code "80") (name "Net-(R28-Pad1)") (class "Default")
      (node (ref "R28") (pin "1") (pinfunction "1_1") (pintype "passive"))
      (node (ref "U$3") (pin "50") (pinfunction "50_50") (pintype "passive"))
    )
    (net (code "81") (name "Net-(R29-Pad1)") (class "Default")
      (node (ref "R29") (pin "1") (pinfunction "1_1") (pintype "passive"))
      (node (ref "U$3") (pin "48") (pinfunction "48_48") (pintype "passive"))
    )
    (net (code "82") (name "Net-(R30-Pad1)") (class "Default")
      (node (ref "R30") (pin "1") (pinfunction "1_1") (pintype "passive"))
      (node (ref "VD1") (pin "A") (pinfunction "A_A") (pintype "passive"))
    )
    (net (code "83") (name "Net-(R31-Pad1)") (class "Default")
      (node (ref "R31") (pin "1") (pinfunction "1_1") (pintype "passive"))
      (node (ref "U$3") (pin "46") (pinfunction "46_46") (pintype "passive"))
    )
    (net (code "84") (name "Net-(R32-Pad1)") (class "Default")
      (node (ref "R32") (pin "1") (pinfunction "1_1") (pintype "passive"))
      (node (ref "U$3") (pin "44") (pinfunction "44_44") (pintype "passive"))
    )
    (net (code "85") (name "Net-(R33-Pad1)") (class "Default")
      (node (ref "R33") (pin "1") (pinfunction "1_1") (pintype "passive"))
      (node (ref "U$3") (pin "42") (pinfunction "42_42") (pintype "passive"))
    )
    (net (code "86") (name "Net-(R34-Pad1)") (class "Default")
      (node (ref "R34") (pin "1") (pinfunction "1_1") (pintype "passive"))
      (node (ref "U$3") (pin "8") (pinfunction "8_8") (pintype "passive"))
    )
    (net (code "87") (name "Net-(R35-Pad1)") (class "Default")
      (node (ref "R35") (pin "1") (pinfunction "1_1") (pintype "passive"))
      (node (ref "U$3") (pin "6") (pinfunction "6_6") (pintype "passive"))
    )
    (net (code "88") (name "Net-(R36-Pad1)") (class "Default")
      (node (ref "R36") (pin "1") (pinfunction "1_1") (pintype "passive"))
      (node (ref "U$3") (pin "4") (pinfunction "4_4") (pintype "passive"))
    )
    (net (code "89") (name "Net-(R37-Pad1)") (class "Default")
      (node (ref "R37") (pin "1") (pinfunction "1_1") (pintype "passive"))
      (node (ref "U$3") (pin "2") (pinfunction "2_2") (pintype "passive"))
    )
    (net (code "90") (name "Net-(R60-Pad1)") (class "Default")
      (node (ref "R60") (pin "1") (pinfunction "1_1") (pintype "passive"))
      (node (ref "VD2") (pin "A") (pinfunction "A_A") (pintype "passive"))
    )
    (net (code "91") (name "Net-(U$4-PH0(OSC_IN))") (class "Default")
      (node (ref "C12") (pin "2") (pinfunction "2_2") (pintype "passive"))
      (node (ref "U$4") (pin "29") (pinfunction "PH0(OSC_IN)_29") (pintype "bidirectional"))
      (node (ref "ZQ1") (pin "3") (pinfunction "2_3") (pintype "passive"))
    )
    (net (code "92") (name "Net-(U$4-PH1(OSC_OUT))") (class "Default")
      (node (ref "C11") (pin "2") (pinfunction "2_2") (pintype "passive"))
      (node (ref "U$4") (pin "30") (pinfunction "PH1(OSC_OUT)_30") (pintype "bidirectional"))
      (node (ref "ZQ1") (pin "1") (pinfunction "1_1") (pintype "passive"))
    )
    (net (code "93") (name "Net-(U$4-VCAP_1)") (class "Default")
      (node (ref "C7") (pin "2") (pinfunction "2_2") (pintype "passive"))
      (node (ref "U$4") (pin "81") (pinfunction "VCAP_1_81") (pintype "power_in"))
    )
    (net (code "94") (name "Net-(U$4-VCAP_2)") (class "Default")
      (node (ref "C23") (pin "2") (pinfunction "2_2") (pintype "passive"))
      (node (ref "U$4") (pin "125") (pinfunction "VCAP_2_125") (pintype "power_in"))
    )
    (net (code "95") (name "USB_DM") (class "Default")
      (node (ref "U$4") (pin "122") (pinfunction "PA11_122") (pintype "bidirectional"))
      (node (ref "X1") (pin "D-") (pinfunction "D-_D-") (pintype "bidirectional"))
    )
    (net (code "96") (name "USB_DP") (class "Default")
      (node (ref "U$4") (pin "123") (pinfunction "PA12_123") (pintype "bidirectional"))
      (node (ref "X1") (pin "D+") (pinfunction "D+_D+") (pintype "bidirectional"))
    )
    (net (code "97") (name "USB_PRESENT") (class "Default")
      (node (ref "R1") (pin "1") (pinfunction "1_1") (pintype "passive"))
      (node (ref "U$4") (pin "121") (pinfunction "PA10_121") (pintype "bidirectional"))
    )
    (net (code "98") (name "unconnected-(U$4-BOOT_1(PB2)-Pad58)") (class "Default")
      (node (ref "U$4") (pin "58") (pinfunction "BOOT_1(PB2)_58") (pintype "bidirectional"))
    )
    (net (code "99") (name "unconnected-(U$4-PA0-Pad40)") (class "Default")
      (node (ref "U$4") (pin "40") (pinfunction "PA0_40") (pintype "bidirectional"))
    )
    (net (code "100") (name "unconnected-(U$4-PA1-Pad41)") (class "Default")
      (node (ref "U$4") (pin "41") (pinfunction "PA1_41") (pintype "bidirectional"))
    )
    (net (code "101") (name "unconnected-(U$4-PA2-Pad42)") (class "Default")
      (node (ref "U$4") (pin "42") (pinfunction "PA2_42") (pintype "bidirectional"))
    )
    (net (code "102") (name "unconnected-(U$4-PA3-Pad47)") (class "Default")
      (node (ref "U$4") (pin "47") (pinfunction "PA3_47") (pintype "bidirectional"))
    )
    (net (code "103") (name "unconnected-(U$4-PA4-Pad50)") (class "Default")
      (node (ref "U$4") (pin "50") (pinfunction "PA4_50") (pintype "bidirectional"))
    )
    (net (code "104") (name "unconnected-(U$4-PA5-Pad51)") (class "Default")
      (node (ref "U$4") (pin "51") (pinfunction "PA5_51") (pintype "bidirectional"))
    )
    (net (code "105") (name "unconnected-(U$4-PA6-Pad52)") (class "Default")
      (node (ref "U$4") (pin "52") (pinfunction "PA6_52") (pintype "bidirectional"))
    )
    (net (code "106") (name "unconnected-(U$4-PA7-Pad53)") (class "Default")
      (node (ref "U$4") (pin "53") (pinfunction "PA7_53") (pintype "bidirectional"))
    )
    (net (code "107") (name "unconnected-(U$4-PA8-Pad119)") (class "Default")
      (node (ref "U$4") (pin "119") (pinfunction "PA8_119") (pintype "bidirectional"))
    )
    (net (code "108") (name "unconnected-(U$4-PA9-Pad120)") (class "Default")
      (node (ref "U$4") (pin "120") (pinfunction "PA9_120") (pintype "bidirectional"))
    )
    (net (code "109") (name "unconnected-(U$4-PB0-Pad56)") (class "Default")
      (node (ref "U$4") (pin "56") (pinfunction "PB0_56") (pintype "bidirectional"))
    )
    (net (code "110") (name "unconnected-(U$4-PB1-Pad57)") (class "Default")
      (node (ref "U$4") (pin "57") (pinfunction "PB1_57") (pintype "bidirectional"))
    )
    (net (code "111") (name "unconnected-(U$4-PB5-Pad163)") (class "Default")
      (node (ref "U$4") (pin "163") (pinfunction "PB5_163") (pintype "bidirectional"))
    )
    (net (code "112") (name "unconnected-(U$4-PB6-Pad164)") (class "Default")
      (node (ref "U$4") (pin "164") (pinfunction "PB6_164") (pintype "bidirectional"))
    )
    (net (code "113") (name "unconnected-(U$4-PB7-Pad165)") (class "Default")
      (node (ref "U$4") (pin "165") (pinfunction "PB7_165") (pintype "bidirectional"))
    )
    (net (code "114") (name "unconnected-(U$4-PB8-Pad167)") (class "Default")
      (node (ref "U$4") (pin "167") (pinfunction "PB8_167") (pintype "bidirectional"))
    )
    (net (code "115") (name "unconnected-(U$4-PB9-Pad168)") (class "Default")
      (node (ref "U$4") (pin "168") (pinfunction "PB9_168") (pintype "bidirectional"))
    )
    (net (code "116") (name "unconnected-(U$4-PB10-Pad79)") (class "Default")
      (node (ref "U$4") (pin "79") (pinfunction "PB10_79") (pintype "bidirectional"))
    )
    (net (code "117") (name "unconnected-(U$4-PB11-Pad80)") (class "Default")
      (node (ref "U$4") (pin "80") (pinfunction "PB11_80") (pintype "bidirectional"))
    )
    (net (code "118") (name "unconnected-(U$4-PB12-Pad92)") (class "Default")
      (node (ref "U$4") (pin "92") (pinfunction "PB12_92") (pintype "bidirectional"))
    )
    (net (code "119") (name "unconnected-(U$4-PB13-Pad93)") (class "Default")
      (node (ref "U$4") (pin "93") (pinfunction "PB13_93") (pintype "bidirectional"))
    )
    (net (code "120") (name "unconnected-(U$4-PB14-Pad94)") (class "Default")
      (node (ref "U$4") (pin "94") (pinfunction "PB14_94") (pintype "bidirectional"))
    )
    (net (code "121") (name "unconnected-(U$4-PB15-Pad95)") (class "Default")
      (node (ref "U$4") (pin "95") (pinfunction "PB15_95") (pintype "bidirectional"))
    )
    (net (code "122") (name "unconnected-(U$4-PC0-Pad32)") (class "Default")
      (node (ref "U$4") (pin "32") (pinfunction "PC0_32") (pintype "bidirectional"))
    )
    (net (code "123") (name "unconnected-(U$4-PC1-Pad33)") (class "Default")
      (node (ref "U$4") (pin "33") (pinfunction "PC1_33") (pintype "bidirectional"))
    )
    (net (code "124") (name "unconnected-(U$4-PC2-Pad34)") (class "Default")
      (node (ref "U$4") (pin "34") (pinfunction "PC2_34") (pintype "bidirectional"))
    )
    (net (code "125") (name "unconnected-(U$4-PC3-Pad35)") (class "Default")
      (node (ref "U$4") (pin "35") (pinfunction "PC3_35") (pintype "bidirectional"))
    )
    (net (code "126") (name "unconnected-(U$4-PC4-Pad54)") (class "Default")
      (node (ref "U$4") (pin "54") (pinfunction "PC4_54") (pintype "bidirectional"))
    )
    (net (code "127") (name "unconnected-(U$4-PC5-Pad55)") (class "Default")
      (node (ref "U$4") (pin "55") (pinfunction "PC5_55") (pintype "bidirectional"))
    )
    (net (code "128") (name "unconnected-(U$4-PC6-Pad115)") (class "Default")
      (node (ref "U$4") (pin "115") (pinfunction "PC6_115") (pintype "bidirectional"))
    )
    (net (code "129") (name "unconnected-(U$4-PC7-Pad116)") (class "Default")
      (node (ref "U$4") (pin "116") (pinfunction "PC7_116") (pintype "bidirectional"))
    )
    (net (code "130") (name "unconnected-(U$4-PC8-Pad117)") (class "Default")
      (node (ref "U$4") (pin "117") (pinfunction "PC8_117") (pintype "bidirectional"))
    )
    (net (code "131") (name "unconnected-(U$4-PC9-Pad118)") (class "Default")
      (node (ref "U$4") (pin "118") (pinfunction "PC9_118") (pintype "bidirectional"))
    )
    (net (code "132") (name "unconnected-(U$4-PC10-Pad139)") (class "Default")
      (node (ref "U$4") (pin "139") (pinfunction "PC10_139") (pintype "bidirectional"))
    )
    (net (code "133") (name "unconnected-(U$4-PC11-Pad140)") (class "Default")
      (node (ref "U$4") (pin "140") (pinfunction "PC11_140") (pintype "bidirectional"))
    )
    (net (code "134") (name "unconnected-(U$4-PC12-Pad141)") (class "Default")
      (node (ref "U$4") (pin "141") (pinfunction "PC12_141") (pintype "bidirectional"))
    )
    (net (code "135") (name "unconnected-(U$4-PC13(TAMPER-RTC)-Pad8)") (class "Default")
      (node (ref "U$4") (pin "8") (pinfunction "PC13(TAMPER-RTC)_8") (pintype "bidirectional"))
    )
    (net (code "136") (name "unconnected-(U$4-PC14(OSC32_IN)-Pad9)") (class "Default")
      (node (ref "U$4") (pin "9") (pinfunction "PC14(OSC32_IN)_9") (pintype "bidirectional"))
    )
    (net (code "137") (name "unconnected-(U$4-PC15(OSC32_OUT)-Pad10)") (class "Default")
      (node (ref "U$4") (pin "10") (pinfunction "PC15(OSC32_OUT)_10") (pintype "bidirectional"))
    )
    (net (code "138") (name "unconnected-(U$4-PD2-Pad144)") (class "Default")
      (node (ref "U$4") (pin "144") (pinfunction "PD2_144") (pintype "bidirectional"))
    )
    (net (code "139") (name "unconnected-(U$4-PD3-Pad145)") (class "Default")
      (node (ref "U$4") (pin "145") (pinfunction "PD3_145") (pintype "bidirectional"))
    )
    (net (code "140") (name "unconnected-(U$4-PD6-Pad150)") (class "Default")
      (node (ref "U$4") (pin "150") (pinfunction "PD6_150") (pintype "bidirectional"))
    )
    (net (code "141") (name "unconnected-(U$4-PD11-Pad99)") (class "Default")
      (node (ref "U$4") (pin "99") (pinfunction "PD11_99") (pintype "bidirectional"))
    )
    (net (code "142") (name "unconnected-(U$4-PD12-Pad100)") (class "Default")
      (node (ref "U$4") (pin "100") (pinfunction "PD12_100") (pintype "bidirectional"))
    )
    (net (code "143") (name "unconnected-(U$4-PD13-Pad101)") (class "Default")
      (node (ref "U$4") (pin "101") (pinfunction "PD13_101") (pintype "bidirectional"))
    )
    (net (code "144") (name "unconnected-(U$4-PE2-Pad1)") (class "Default")
      (node (ref "U$4") (pin "1") (pinfunction "PE2_1") (pintype "bidirectional"))
    )
    (net (code "145") (name "unconnected-(U$4-PE6-Pad5)") (class "Default")
      (node (ref "U$4") (pin "5") (pinfunction "PE6_5") (pintype "bidirectional"))
    )
    (net (code "146") (name "unconnected-(U$4-PF6-Pad24)") (class "Default")
      (node (ref "U$4") (pin "24") (pinfunction "PF6_24") (pintype "bidirectional"))
    )
    (net (code "147") (name "unconnected-(U$4-PF7-Pad25)") (class "Default")
      (node (ref "U$4") (pin "25") (pinfunction "PF7_25") (pintype "bidirectional"))
    )
    (net (code "148") (name "unconnected-(U$4-PF8-Pad26)") (class "Default")
      (node (ref "U$4") (pin "26") (pinfunction "PF8_26") (pintype "bidirectional"))
    )
    (net (code "149") (name "unconnected-(U$4-PF9-Pad27)") (class "Default")
      (node (ref "U$4") (pin "27") (pinfunction "PF9_27") (pintype "bidirectional"))
    )
    (net (code "150") (name "unconnected-(U$4-PF10-Pad28)") (class "Default")
      (node (ref "U$4") (pin "28") (pinfunction "PF10_28") (pintype "bidirectional"))
    )
    (net (code "151") (name "unconnected-(U$4-PF11-Pad59)") (class "Default")
      (node (ref "U$4") (pin "59") (pinfunction "PF11_59") (pintype "bidirectional"))
    )
    (net (code "152") (name "unconnected-(U$4-PG6-Pad110)") (class "Default")
      (node (ref "U$4") (pin "110") (pinfunction "PG6_110") (pintype "bidirectional"))
    )
    (net (code "153") (name "unconnected-(U$4-PG7-Pad111)") (class "Default")
      (node (ref "U$4") (pin "111") (pinfunction "PG7_111") (pintype "bidirectional"))
    )
    (net (code "154") (name "unconnected-(U$4-PG8-Pad112)") (class "Default")
      (node (ref "U$4") (pin "112") (pinfunction "PG8_112") (pintype "bidirectional"))
    )
    (net (code "155") (name "unconnected-(U$4-PG9-Pad152)") (class "Default")
      (node (ref "U$4") (pin "152") (pinfunction "PG9_152") (pintype "bidirectional"))
    )
    (net (code "156") (name "unconnected-(U$4-PG10-Pad153)") (class "Default")
      (node (ref "U$4") (pin "153") (pinfunction "PG10_153") (pintype "bidirectional"))
    )
    (net (code "157") (name "unconnected-(U$4-PG11-Pad154)") (class "Default")
      (node (ref "U$4") (pin "154") (pinfunction "PG11_154") (pintype "bidirectional"))
    )
    (net (code "158") (name "unconnected-(U$4-PG12-Pad155)") (class "Default")
      (node (ref "U$4") (pin "155") (pinfunction "PG12_155") (pintype "bidirectional"))
    )
    (net (code "159") (name "unconnected-(U$4-PG13-Pad156)") (class "Default")
      (node (ref "U$4") (pin "156") (pinfunction "PG13_156") (pintype "bidirectional"))
    )
    (net (code "160") (name "unconnected-(U$4-PG14-Pad157)") (class "Default")
      (node (ref "U$4") (pin "157") (pinfunction "PG14_157") (pintype "bidirectional"))
    )
    (net (code "161") (name "unconnected-(U$4-PG15-Pad160)") (class "Default")
      (node (ref "U$4") (pin "160") (pinfunction "PG15_160") (pintype "bidirectional"))
    )
    (net (code "162") (name "unconnected-(U$4-PH2-Pad43)") (class "Default")
      (node (ref "U$4") (pin "43") (pinfunction "PH2_43") (pintype "bidirectional"))
    )
    (net (code "163") (name "unconnected-(U$4-PH3-Pad44)") (class "Default")
      (node (ref "U$4") (pin "44") (pinfunction "PH3_44") (pintype "bidirectional"))
    )
    (net (code "164") (name "unconnected-(U$4-PH4-Pad45)") (class "Default")
      (node (ref "U$4") (pin "45") (pinfunction "PH4_45") (pintype "bidirectional"))
    )
    (net (code "165") (name "unconnected-(U$4-PH5-Pad46)") (class "Default")
      (node (ref "U$4") (pin "46") (pinfunction "PH5_46") (pintype "bidirectional"))
    )
    (net (code "166") (name "unconnected-(U$4-PH6-Pad83)") (class "Default")
      (node (ref "U$4") (pin "83") (pinfunction "PH6_83") (pintype "bidirectional"))
    )
    (net (code "167") (name "unconnected-(U$4-PH7-Pad84)") (class "Default")
      (node (ref "U$4") (pin "84") (pinfunction "PH7_84") (pintype "bidirectional"))
    )
    (net (code "168") (name "unconnected-(U$4-PH8-Pad85)") (class "Default")
      (node (ref "U$4") (pin "85") (pinfunction "PH8_85") (pintype "bidirectional"))
    )
    (net (code "169") (name "unconnected-(U$4-PH9-Pad86)") (class "Default")
      (node (ref "U$4") (pin "86") (pinfunction "PH9_86") (pintype "bidirectional"))
    )
    (net (code "170") (name "unconnected-(U$4-PH10-Pad87)") (class "Default")
      (node (ref "U$4") (pin "87") (pinfunction "PH10_87") (pintype "bidirectional"))
    )
    (net (code "171") (name "unconnected-(U$4-PH11-Pad88)") (class "Default")
      (node (ref "U$4") (pin "88") (pinfunction "PH11_88") (pintype "bidirectional"))
    )
    (net (code "172") (name "unconnected-(U$4-PH12-Pad89)") (class "Default")
      (node (ref "U$4") (pin "89") (pinfunction "PH12_89") (pintype "bidirectional"))
    )
    (net (code "173") (name "unconnected-(U$4-PH13-Pad128)") (class "Default")
      (node (ref "U$4") (pin "128") (pinfunction "PH13_128") (pintype "bidirectional"))
    )
    (net (code "174") (name "unconnected-(U$4-PH14-Pad129)") (class "Default")
      (node (ref "U$4") (pin "129") (pinfunction "PH14_129") (pintype "bidirectional"))
    )
    (net (code "175") (name "unconnected-(U$4-PH15-Pad130)") (class "Default")
      (node (ref "U$4") (pin "130") (pinfunction "PH15_130") (pintype "bidirectional"))
    )
    (net (code "176") (name "unconnected-(U$4-PI0-Pad131)") (class "Default")
      (node (ref "U$4") (pin "131") (pinfunction "PI0_131") (pintype "bidirectional"))
    )
    (net (code "177") (name "unconnected-(U$4-PI1-Pad132)") (class "Default")
      (node (ref "U$4") (pin "132") (pinfunction "PI1_132") (pintype "bidirectional"))
    )
    (net (code "178") (name "unconnected-(U$4-PI4-Pad173)") (class "Default")
      (node (ref "U$4") (pin "173") (pinfunction "PI4_173") (pintype "bidirectional"))
    )
    (net (code "179") (name "unconnected-(U$4-PI5-Pad174)") (class "Default")
      (node (ref "U$4") (pin "174") (pinfunction "PI5_174") (pintype "bidirectional"))
    )
    (net (code "180") (name "unconnected-(U$4-PI6-Pad175)") (class "Default")
      (node (ref "U$4") (pin "175") (pinfunction "PI6_175") (pintype "bidirectional"))
    )
    (net (code "181") (name "unconnected-(U$4-PI7-Pad176)") (class "Default")
      (node (ref "U$4") (pin "176") (pinfunction "PI7_176") (pintype "bidirectional"))
    )
    (net (code "182") (name "unconnected-(U$4-PI8-Pad7)") (class "Default")
      (node (ref "U$4") (pin "7") (pinfunction "PI8_7") (pintype "bidirectional"))
    )
    (net (code "183") (name "unconnected-(U$4-PI9-Pad11)") (class "Default")
      (node (ref "U$4") (pin "11") (pinfunction "PI9_11") (pintype "bidirectional"))
    )
    (net (code "184") (name "unconnected-(U$4-PI10-Pad12)") (class "Default")
      (node (ref "U$4") (pin "12") (pinfunction "PI10_12") (pintype "bidirectional"))
    )
    (net (code "185") (name "unconnected-(U$4-PI11-Pad13)") (class "Default")
      (node (ref "U$4") (pin "13") (pinfunction "PI11_13") (pintype "bidirectional"))
    )
    (net (code "186") (name "unconnected-(XP1-Pad11)") (class "Default")
      (node (ref "XP1") (pin "11") (pinfunction "11_11") (pintype "passive"))
    )
    (net (code "187") (name "unconnected-(XP1-Pad17)") (class "Default")
      (node (ref "XP1") (pin "17") (pinfunction "17_17") (pintype "passive"))
    )
    (net (code "188") (name "unconnected-(XP1-Pad19)") (class "Default")
      (node (ref "XP1") (pin "19") (pinfunction "19_19") (pintype "passive"))
    )
  )
)
